# LSM9DS1-Breakout.net
KiCad netlist of a schematic drawn in EAGLE
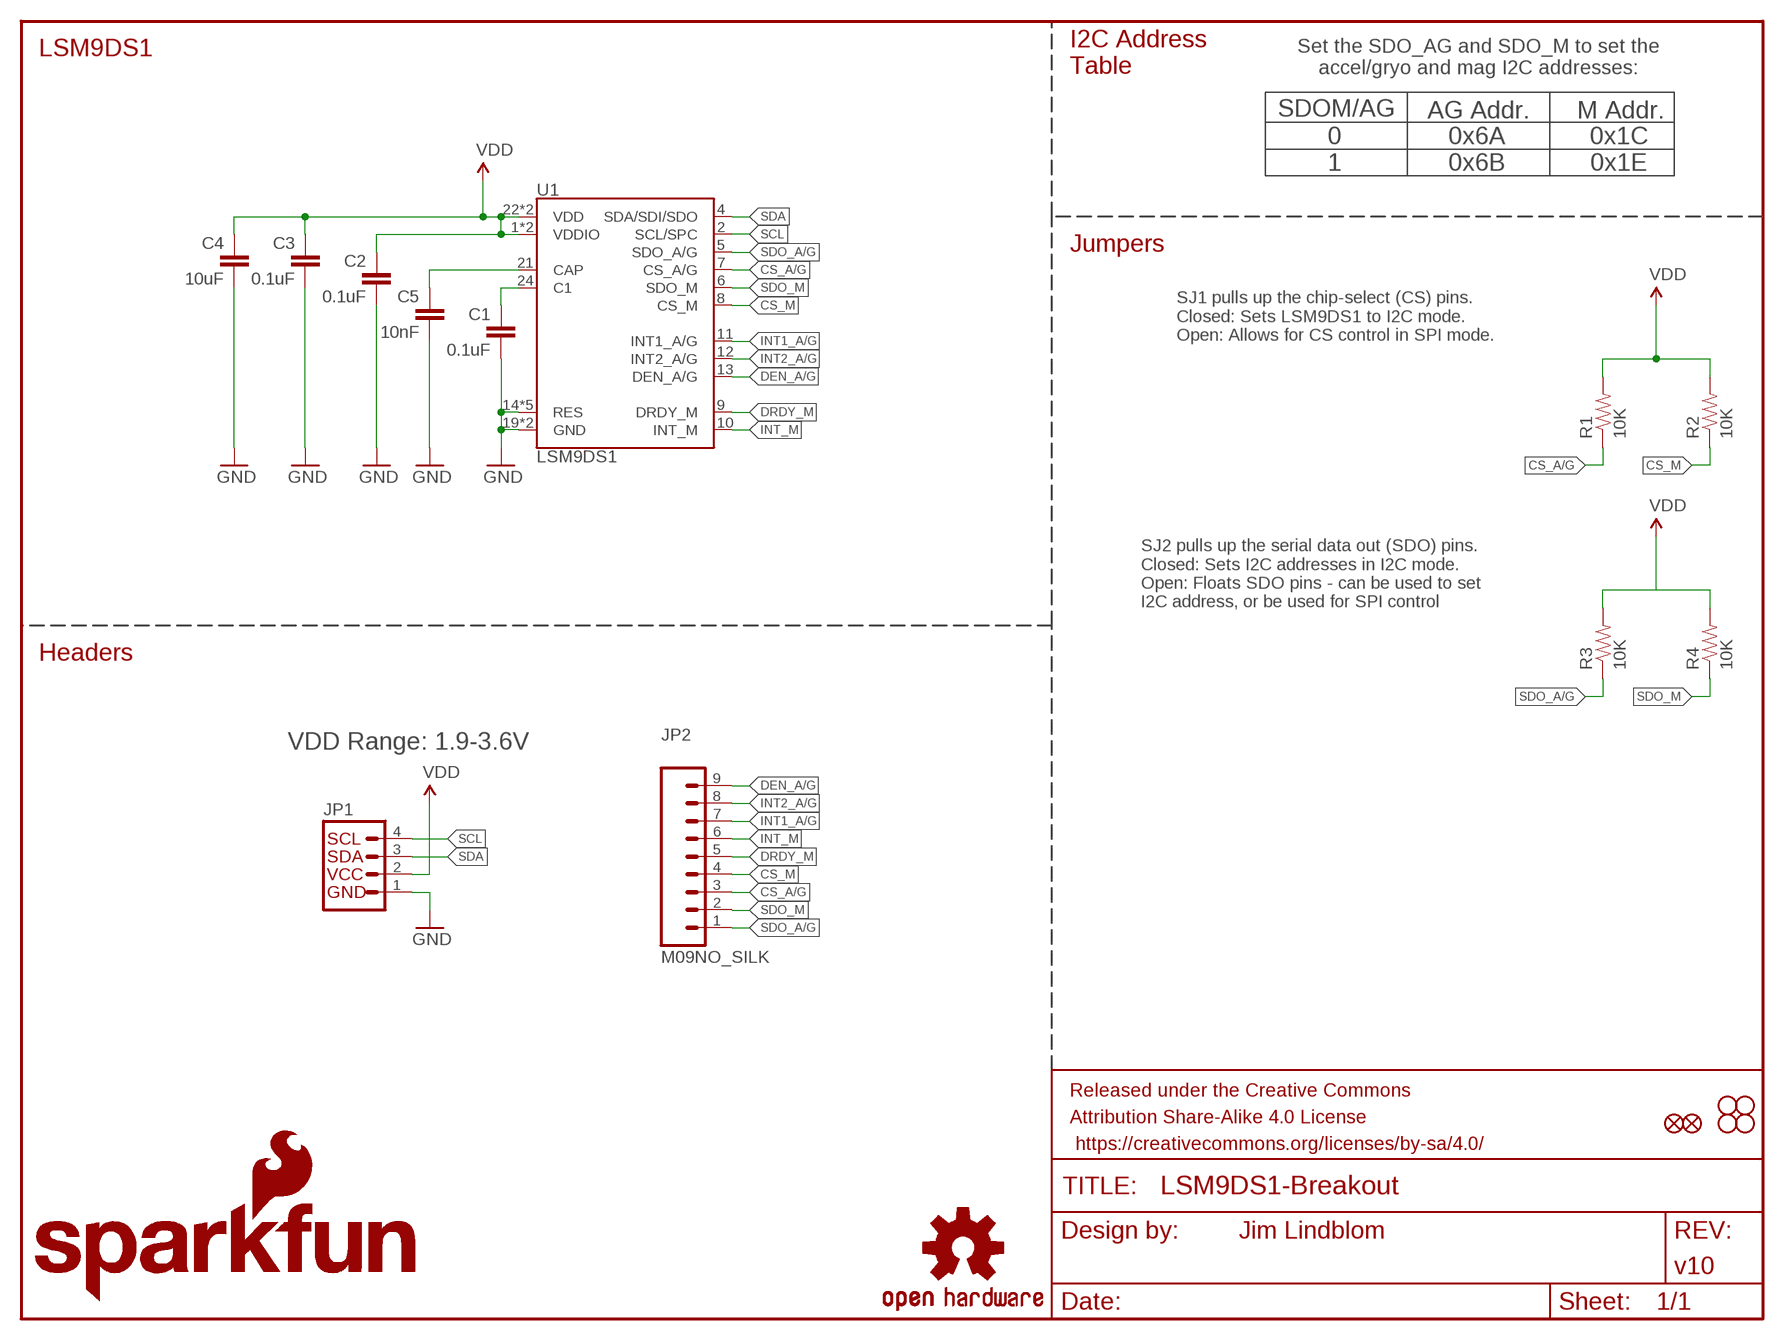
[diagram p0: schematic, sheet 1]

(export (version "E")
  (design (tool "Eeschema 10.0.6"))
  (components
    (comp (ref "C1")
      (value "0.1uF")
      (footprint "eagle-import:0603-CAP")
      (libsource (lib "eagle-import") (part "0.1UF-25V(+80/-20%)(0603)"))
    )
    (comp (ref "C2")
      (value "0.1uF")
      (footprint "eagle-import:0603-CAP")
      (libsource (lib "eagle-import") (part "0.1UF-25V(+80/-20%)(0603)"))
    )
    (comp (ref "C3")
      (value "0.1uF")
      (footprint "eagle-import:0603-CAP")
      (libsource (lib "eagle-import") (part "0.1UF-25V(+80/-20%)(0603)"))
    )
    (comp (ref "C4")
      (value "10uF")
      (footprint "eagle-import:0603-CAP")
      (libsource (lib "eagle-import") (part "10UF-6.3V-20%(0603)"))
    )
    (comp (ref "C5")
      (value "10nF")
      (footprint "eagle-import:0603-CAP")
      (libsource (lib "eagle-import") (part "10NF/10000PF-50V-10%(0603)"))
    )
    (comp (ref "FID1")
      (value "FIDUCIAL1X2")
      (footprint "eagle-import:FIDUCIAL-1X2")
      (libsource (lib "eagle-import") (part "FIDUCIAL1X2"))
    )
    (comp (ref "FID2")
      (value "FIDUCIAL1X2")
      (footprint "eagle-import:FIDUCIAL-1X2")
      (libsource (lib "eagle-import") (part "FIDUCIAL1X2"))
    )
    (comp (ref "FRAME1")
      (value "FRAME-LETTER")
      (footprint "eagle-import:CREATIVE_COMMONS")
      (fields
        (field (name "DESIGNER") "Jim Lindblom")
        (field (name "VERSION") "v10")
        (field (name "DESIGNER_1") "Jim Lindblom")
        (field (name "VERSION_1") "v10")
      )
      (libsource (lib "eagle-import") (part "FRAME-LETTER"))
    )
    (comp (ref "JP1")
      (value "I2C_STANDARD_NO_SILK")
      (footprint "eagle-import:1X04_NO_SILK")
      (libsource (lib "eagle-import") (part "I2C_STANDARD_NO_SILK"))
    )
    (comp (ref "JP2")
      (value "M09NO_SILK")
      (footprint "eagle-import:1X09_NO_SILK")
      (libsource (lib "eagle-import") (part "M09NO_SILK"))
    )
    (comp (ref "LOGO1")
      (value "SFE_LOGO_NAME.1_INCH")
      (footprint "eagle-import:SFE_LOGO_NAME_.1")
      (libsource (lib "eagle-import") (part "SFE_LOGO_NAME.1_INCH"))
    )
    (comp (ref "LOGO2")
      (value "SFE_LOGO_FLAME.2_INCH")
      (footprint "eagle-import:SFE_LOGO_FLAME_.2")
      (libsource (lib "eagle-import") (part "SFE_LOGO_FLAME.2_INCH"))
    )
    (comp (ref "LOGO3")
      (value "OSHW-LOGOS")
      (footprint "eagle-import:OSHW-LOGO-S")
      (libsource (lib "eagle-import") (part "OSHW-LOGOS"))
    )
    (comp (ref "R1")
      (value "10K")
      (footprint "eagle-import:0603-RES")
      (libsource (lib "eagle-import") (part "10KOHM-1/10W-1%(0603)0603"))
    )
    (comp (ref "R2")
      (value "10K")
      (footprint "eagle-import:0603-RES")
      (libsource (lib "eagle-import") (part "10KOHM-1/10W-1%(0603)0603"))
    )
    (comp (ref "R3")
      (value "10K")
      (footprint "eagle-import:0603-RES")
      (libsource (lib "eagle-import") (part "10KOHM-1/10W-1%(0603)0603"))
    )
    (comp (ref "R4")
      (value "10K")
      (footprint "eagle-import:0603-RES")
      (libsource (lib "eagle-import") (part "10KOHM-1/10W-1%(0603)0603"))
    )
    (comp (ref "STANDOFF1")
      (value "STAND-OFF")
      (footprint "eagle-import:STAND-OFF")
      (libsource (lib "eagle-import") (part "STAND-OFF"))
    )
    (comp (ref "STANDOFF2")
      (value "STAND-OFF")
      (footprint "eagle-import:STAND-OFF")
      (libsource (lib "eagle-import") (part "STAND-OFF"))
    )
    (comp (ref "STANDOFF3")
      (value "STAND-OFF")
      (footprint "eagle-import:STAND-OFF")
      (libsource (lib "eagle-import") (part "STAND-OFF"))
    )
    (comp (ref "STANDOFF4")
      (value "STAND-OFF")
      (footprint "eagle-import:STAND-OFF")
      (libsource (lib "eagle-import") (part "STAND-OFF"))
    )
    (comp (ref "U1")
      (value "LSM9DS1")
      (footprint "eagle-import:LGA24-8X4")
      (libsource (lib "eagle-import") (part "LSM9DS1"))
    )
  )
  (nets
    (net (code "1") (name "CS_A{slash}G") (class "Default")
      (node (ref "JP2") (pin "3") (pinfunction "3_3") (pintype "passive"))
      (node (ref "R1") (pin "1") (pinfunction "1_1") (pintype "passive"))
      (node (ref "U1") (pin "7") (pinfunction "CS_A/G_7") (pintype "bidirectional"))
    )
    (net (code "2") (name "CS_M") (class "Default")
      (node (ref "JP2") (pin "4") (pinfunction "4_4") (pintype "passive"))
      (node (ref "R2") (pin "1") (pinfunction "1_1") (pintype "passive"))
      (node (ref "U1") (pin "8") (pinfunction "CS_M_8") (pintype "bidirectional"))
    )
    (net (code "3") (name "DEN_A{slash}G") (class "Default")
      (node (ref "JP2") (pin "9") (pinfunction "9_9") (pintype "passive"))
      (node (ref "U1") (pin "13") (pinfunction "DEN_A/G_13") (pintype "bidirectional"))
    )
    (net (code "4") (name "DRDY_M") (class "Default")
      (node (ref "JP2") (pin "5") (pinfunction "5_5") (pintype "passive"))
      (node (ref "U1") (pin "9") (pinfunction "DRDY_M_9") (pintype "bidirectional"))
    )
    (net (code "5") (name "GND") (class "Default")
      (node (ref "C1") (pin "2") (pinfunction "2_2") (pintype "passive"))
      (node (ref "C2") (pin "2") (pinfunction "2_2") (pintype "passive"))
      (node (ref "C3") (pin "2") (pinfunction "2_2") (pintype "passive"))
      (node (ref "C4") (pin "2") (pinfunction "2_2") (pintype "passive"))
      (node (ref "C5") (pin "2") (pinfunction "2_2") (pintype "passive"))
      (node (ref "JP1") (pin "1") (pinfunction "1_1") (pintype "passive"))
      (node (ref "U1") (pin "14") (pinfunction "RES_14") (pintype "bidirectional"))
      (node (ref "U1") (pin "15") (pinfunction "RES_15") (pintype "bidirectional"))
      (node (ref "U1") (pin "16") (pinfunction "RES_16") (pintype "bidirectional"))
      (node (ref "U1") (pin "17") (pinfunction "RES_17") (pintype "bidirectional"))
      (node (ref "U1") (pin "18") (pinfunction "RES_18") (pintype "bidirectional"))
      (node (ref "U1") (pin "19") (pinfunction "GND_19") (pintype "bidirectional"))
      (node (ref "U1") (pin "20") (pinfunction "GND_20") (pintype "bidirectional"))
    )
    (net (code "6") (name "INT1_A{slash}G") (class "Default")
      (node (ref "JP2") (pin "7") (pinfunction "7_7") (pintype "passive"))
      (node (ref "U1") (pin "11") (pinfunction "INT1_A/G_11") (pintype "bidirectional"))
    )
    (net (code "7") (name "INT2_A{slash}G") (class "Default")
      (node (ref "JP2") (pin "8") (pinfunction "8_8") (pintype "passive"))
      (node (ref "U1") (pin "12") (pinfunction "INT2_A/G_12") (pintype "bidirectional"))
    )
    (net (code "8") (name "INT_M") (class "Default")
      (node (ref "JP2") (pin "6") (pinfunction "6_6") (pintype "passive"))
      (node (ref "U1") (pin "10") (pinfunction "INT_M_10") (pintype "bidirectional"))
    )
    (net (code "9") (name "Net-(U1-C1)") (class "Default")
      (node (ref "C1") (pin "1") (pinfunction "1_1") (pintype "passive"))
      (node (ref "U1") (pin "24") (pinfunction "C1_24") (pintype "bidirectional"))
    )
    (net (code "10") (name "Net-(U1-CAP)") (class "Default")
      (node (ref "C5") (pin "1") (pinfunction "1_1") (pintype "passive"))
      (node (ref "U1") (pin "21") (pinfunction "CAP_21") (pintype "bidirectional"))
    )
    (net (code "11") (name "SCL") (class "Default")
      (node (ref "JP1") (pin "4") (pinfunction "4_4") (pintype "passive"))
      (node (ref "U1") (pin "2") (pinfunction "SCL/SPC_2") (pintype "bidirectional"))
    )
    (net (code "12") (name "SDA") (class "Default")
      (node (ref "JP1") (pin "3") (pinfunction "3_3") (pintype "passive"))
      (node (ref "U1") (pin "4") (pinfunction "SDA/SDI/SDO_4") (pintype "bidirectional"))
    )
    (net (code "13") (name "SDO_A{slash}G") (class "Default")
      (node (ref "JP2") (pin "1") (pinfunction "1_1") (pintype "passive"))
      (node (ref "R3") (pin "1") (pinfunction "1_1") (pintype "passive"))
      (node (ref "U1") (pin "5") (pinfunction "SDO_A/G_5") (pintype "bidirectional"))
    )
    (net (code "14") (name "SDO_M") (class "Default")
      (node (ref "JP2") (pin "2") (pinfunction "2_2") (pintype "passive"))
      (node (ref "R4") (pin "1") (pinfunction "1_1") (pintype "passive"))
      (node (ref "U1") (pin "6") (pinfunction "SDO_M_6") (pintype "bidirectional"))
    )
    (net (code "15") (name "VDD") (class "Default")
      (node (ref "C2") (pin "1") (pinfunction "1_1") (pintype "passive"))
      (node (ref "C3") (pin "1") (pinfunction "1_1") (pintype "passive"))
      (node (ref "C4") (pin "1") (pinfunction "1_1") (pintype "passive"))
      (node (ref "JP1") (pin "2") (pinfunction "2_2") (pintype "passive"))
      (node (ref "R1") (pin "2") (pinfunction "2_2") (pintype "passive"))
      (node (ref "R2") (pin "2") (pinfunction "2_2") (pintype "passive"))
      (node (ref "R3") (pin "2") (pinfunction "2_2") (pintype "passive"))
      (node (ref "R4") (pin "2") (pinfunction "2_2") (pintype "passive"))
      (node (ref "U1") (pin "1") (pinfunction "VDDIO_1") (pintype "bidirectional"))
      (node (ref "U1") (pin "22") (pinfunction "VDD_22") (pintype "bidirectional"))
      (node (ref "U1") (pin "23") (pinfunction "VDD_23") (pintype "bidirectional"))
      (node (ref "U1") (pin "3") (pinfunction "VDDIO_3") (pintype "bidirectional"))
    )
  )
)
